# 48V_Converter2.net
KiCad netlist of a schematic drawn in Altium Designer
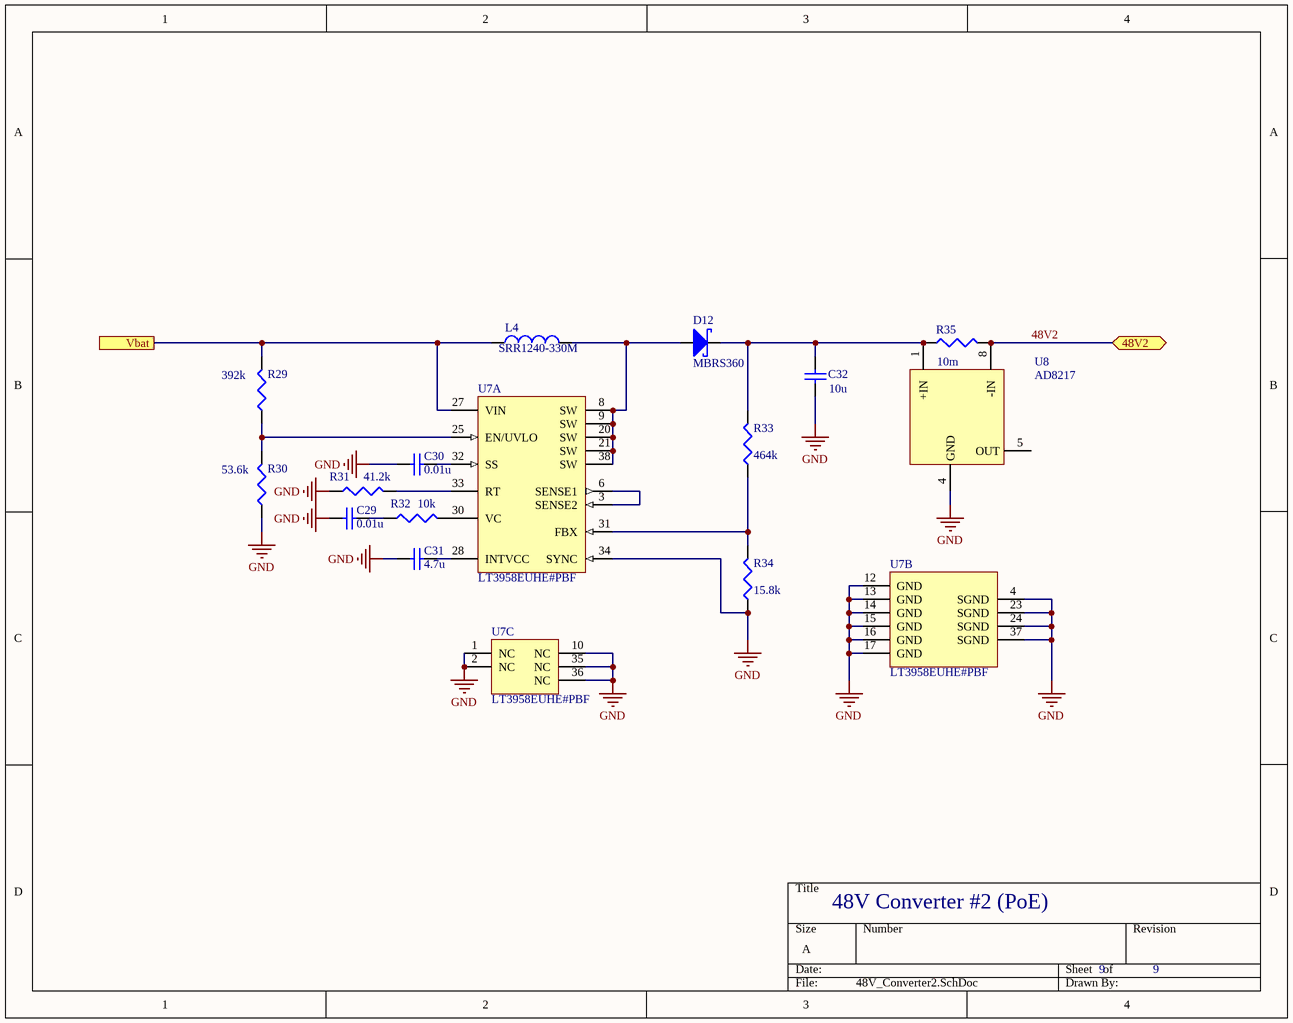
[diagram p0: 48V_Converter2.SchDoc]

(export (version "E")
  (design (tool "Eeschema 10.0.6"))
  (components
    (comp (ref "C29")
      (value "0.01u")
      (footprint "C1206")
      (description "Capacitor (Semiconductor SIM Model)")
      (fields (field (name "Comment") "Cap Semi") (field (name "PUBLISHER") "Altium Limited"))
      (libsource (lib "Miscellaneous Devices") (part "Cap Semi"))
    )
    (comp (ref "C30")
      (value "0.01u")
      (footprint "C1206")
      (description "Capacitor (Semiconductor SIM Model)")
      (fields (field (name "Comment") "Cap Semi") (field (name "PUBLISHER") "Altium Limited"))
      (libsource (lib "Miscellaneous Devices") (part "Cap Semi"))
    )
    (comp (ref "C31")
      (value "4.7u")
      (footprint "C1206")
      (description "Capacitor (Semiconductor SIM Model)")
      (fields (field (name "Comment") "Cap Semi") (field (name "PUBLISHER") "Altium Limited"))
      (libsource (lib "Miscellaneous Devices") (part "Cap Semi"))
    )
    (comp (ref "C32")
      (value "10u")
      (footprint "C1206")
      (description "Capacitor (Semiconductor SIM Model)")
      (fields (field (name "Comment") "Cap Semi") (field (name "PUBLISHER") "Altium Limited"))
      (libsource (lib "Miscellaneous Devices") (part "Cap Semi"))
    )
    (comp (ref "D12")
      (value "MBRS360")
      (footprint "MBRS360")
      (description "DIODE SCHOTTKY 60V 3A SMC")
      (libsource (lib "Power_Embedded_Board_Library") (part "MBRS360"))
    )
    (comp (ref "L4")
      (value "SRR1240-330M")
      (footprint "SRR1240")
      (description "FIXED IND 33UH 2.3A 97 MOHM SMD")
      (libsource (lib "Power_Embedded_Board_Library") (part "SRR1240"))
    )
    (comp (ref "R29")
      (value "392k")
      (footprint "J1-0603")
      (description "Resistor")
      (fields (field (name "Comment") "Res3") (field (name "PUBLISHER") "Altium Limited"))
      (libsource (lib "Miscellaneous Devices") (part "Res3"))
    )
    (comp (ref "R30")
      (value "53.6k")
      (footprint "J1-0603")
      (description "Resistor")
      (fields (field (name "Comment") "Res3") (field (name "PUBLISHER") "Altium Limited"))
      (libsource (lib "Miscellaneous Devices") (part "Res3"))
    )
    (comp (ref "R31")
      (value "41.2k")
      (footprint "J1-0603")
      (description "Resistor")
      (fields (field (name "Comment") "Res3") (field (name "PUBLISHER") "Altium Limited"))
      (libsource (lib "Miscellaneous Devices") (part "Res3"))
    )
    (comp (ref "R32")
      (value "10k")
      (footprint "J1-0603")
      (description "Resistor")
      (fields (field (name "Comment") "Res3") (field (name "PUBLISHER") "Altium Limited"))
      (libsource (lib "Miscellaneous Devices") (part "Res3"))
    )
    (comp (ref "R33")
      (value "464k")
      (footprint "J1-0603")
      (description "Resistor")
      (fields (field (name "Comment") "Res3") (field (name "PUBLISHER") "Altium Limited"))
      (libsource (lib "Miscellaneous Devices") (part "Res3"))
    )
    (comp (ref "R34")
      (value "15.8k")
      (footprint "J1-0603")
      (description "Resistor")
      (fields (field (name "Comment") "Res3") (field (name "PUBLISHER") "Altium Limited"))
      (libsource (lib "Miscellaneous Devices") (part "Res3"))
    )
    (comp (ref "R35")
      (value "10m")
      (footprint "J1-0603")
      (description "Resistor")
      (fields (field (name "Comment") "Res3") (field (name "PUBLISHER") "Altium Limited"))
      (libsource (lib "Miscellaneous Devices") (part "Res3"))
    )
    (comp (ref "U7")
      (value "LT3958EUHE#PBF")
      (footprint "LT-UHE-36-V-UHE28MA_V")
      (fields (field (name "MANUFACTURER") "Linear Technology"))
      (libsource (lib "Power_Embedded_Board_Library") (part "LT3958EUHE#PBF"))
    )
    (comp (ref "U8")
      (value "AD8217")
      (footprint "AD8217")
      (description "High Resolution, Zero-Drift  Current Shunt Monitor")
      (libsource (lib "Power_Embedded_Board_Library") (part "AD8217"))
    )
  )
  (nets
    (net (code "1") (name "/48V2") (class "Default")
      (node (ref "R35") (pin "2") (pinfunction "2_2") (pintype "passive"))
      (node (ref "U8") (pin "8") (pinfunction "-IN_8") (pintype "passive"))
    )
    (net (code "2") (name "/Vbat") (class "Default")
      (node (ref "L4") (pin "1") (pinfunction "1_1") (pintype "passive"))
      (node (ref "R29") (pin "2") (pinfunction "2_2") (pintype "passive"))
      (node (ref "U7") (pin "27") (pinfunction "VIN_27") (pintype "power_in"))
    )
    (net (code "3") (name "GND") (class "Default")
      (node (ref "C29") (pin "1") (pinfunction "1_1") (pintype "passive"))
      (node (ref "C30") (pin "1") (pinfunction "1_1") (pintype "passive"))
      (node (ref "C31") (pin "1") (pinfunction "1_1") (pintype "passive"))
      (node (ref "C32") (pin "1") (pinfunction "1_1") (pintype "passive"))
      (node (ref "R30") (pin "1") (pinfunction "1_1") (pintype "passive"))
      (node (ref "R31") (pin "1") (pinfunction "1_1") (pintype "passive"))
      (node (ref "R34") (pin "1") (pinfunction "1_1") (pintype "passive"))
      (node (ref "U7") (pin "1") (pinfunction "NC_1") (pintype "passive"))
      (node (ref "U7") (pin "10") (pinfunction "NC_10") (pintype "passive"))
      (node (ref "U7") (pin "12") (pinfunction "GND_12") (pintype "power_in"))
      (node (ref "U7") (pin "13") (pinfunction "GND_13") (pintype "power_in"))
      (node (ref "U7") (pin "14") (pinfunction "GND_14") (pintype "power_in"))
      (node (ref "U7") (pin "15") (pinfunction "GND_15") (pintype "power_in"))
      (node (ref "U7") (pin "16") (pinfunction "GND_16") (pintype "power_in"))
      (node (ref "U7") (pin "17") (pinfunction "GND_17") (pintype "power_in"))
      (node (ref "U7") (pin "2") (pinfunction "NC_2") (pintype "passive"))
      (node (ref "U7") (pin "23") (pinfunction "SGND_23") (pintype "power_in"))
      (node (ref "U7") (pin "24") (pinfunction "SGND_24") (pintype "power_in"))
      (node (ref "U7") (pin "34") (pinfunction "SYNC_34") (pintype "input"))
      (node (ref "U7") (pin "35") (pinfunction "NC_35") (pintype "passive"))
      (node (ref "U7") (pin "36") (pinfunction "NC_36") (pintype "passive"))
      (node (ref "U7") (pin "37") (pinfunction "SGND_37") (pintype "power_in"))
      (node (ref "U7") (pin "4") (pinfunction "SGND_4") (pintype "power_in"))
      (node (ref "U8") (pin "4") (pinfunction "GND_4") (pintype "passive"))
    )
    (net (code "4") (name "Net-(C29-Pad2)") (class "Default")
      (node (ref "C29") (pin "2") (pinfunction "2_2") (pintype "passive"))
      (node (ref "R32") (pin "1") (pinfunction "1_1") (pintype "passive"))
    )
    (net (code "5") (name "Net-(D12-Anode)") (class "Default")
      (node (ref "D12") (pin "1") (pinfunction "Anode_1") (pintype "passive"))
      (node (ref "L4") (pin "2") (pinfunction "2_2") (pintype "passive"))
      (node (ref "U7") (pin "20") (pinfunction "SW_20") (pintype "power_in"))
      (node (ref "U7") (pin "21") (pinfunction "SW_21") (pintype "power_in"))
      (node (ref "U7") (pin "38") (pinfunction "SW_38") (pintype "power_in"))
      (node (ref "U7") (pin "8") (pinfunction "SW_8") (pintype "power_in"))
      (node (ref "U7") (pin "9") (pinfunction "SW_9") (pintype "power_in"))
    )
    (net (code "6") (name "Net-(D12-Cathode)") (class "Default")
      (node (ref "C32") (pin "2") (pinfunction "2_2") (pintype "passive"))
      (node (ref "D12") (pin "2") (pinfunction "Cathode_2") (pintype "passive"))
      (node (ref "R33") (pin "2") (pinfunction "2_2") (pintype "passive"))
      (node (ref "R35") (pin "1") (pinfunction "1_1") (pintype "passive"))
      (node (ref "U8") (pin "1") (pinfunction "+IN_1") (pintype "passive"))
    )
    (net (code "7") (name "Net-(U7A-EN{slash}UVLO)") (class "Default")
      (node (ref "R29") (pin "1") (pinfunction "1_1") (pintype "passive"))
      (node (ref "R30") (pin "2") (pinfunction "2_2") (pintype "passive"))
      (node (ref "U7") (pin "25") (pinfunction "EN/UVLO_25") (pintype "input"))
    )
    (net (code "8") (name "Net-(U7A-FBX)") (class "Default")
      (node (ref "R33") (pin "1") (pinfunction "1_1") (pintype "passive"))
      (node (ref "R34") (pin "2") (pinfunction "2_2") (pintype "passive"))
      (node (ref "U7") (pin "31") (pinfunction "FBX_31") (pintype "input"))
    )
    (net (code "9") (name "Net-(U7A-INTVCC)") (class "Default")
      (node (ref "C31") (pin "2") (pinfunction "2_2") (pintype "passive"))
      (node (ref "U7") (pin "28") (pinfunction "INTVCC_28") (pintype "power_in"))
    )
    (net (code "10") (name "Net-(U7A-RT)") (class "Default")
      (node (ref "R31") (pin "2") (pinfunction "2_2") (pintype "passive"))
      (node (ref "U7") (pin "33") (pinfunction "RT_33") (pintype "passive"))
    )
    (net (code "11") (name "Net-(U7A-SENSE1)") (class "Default")
      (node (ref "U7") (pin "3") (pinfunction "SENSE2_3") (pintype "input"))
      (node (ref "U7") (pin "6") (pinfunction "SENSE1_6") (pintype "output"))
    )
    (net (code "12") (name "Net-(U7A-SS)") (class "Default")
      (node (ref "C30") (pin "2") (pinfunction "2_2") (pintype "passive"))
      (node (ref "U7") (pin "32") (pinfunction "SS_32") (pintype "input"))
    )
    (net (code "13") (name "Net-(U7A-VC)") (class "Default")
      (node (ref "R32") (pin "2") (pinfunction "2_2") (pintype "passive"))
      (node (ref "U7") (pin "30") (pinfunction "VC_30") (pintype "passive"))
    )
    (net (code "14") (name "unconnected-(U8-OUT-Pad5)") (class "Default")
      (node (ref "U8") (pin "5") (pinfunction "OUT_5") (pintype "passive"))
    )
  )
)
